# USB_Analog_Controller_24V.net
KiCad netlist of a schematic drawn in EAGLE
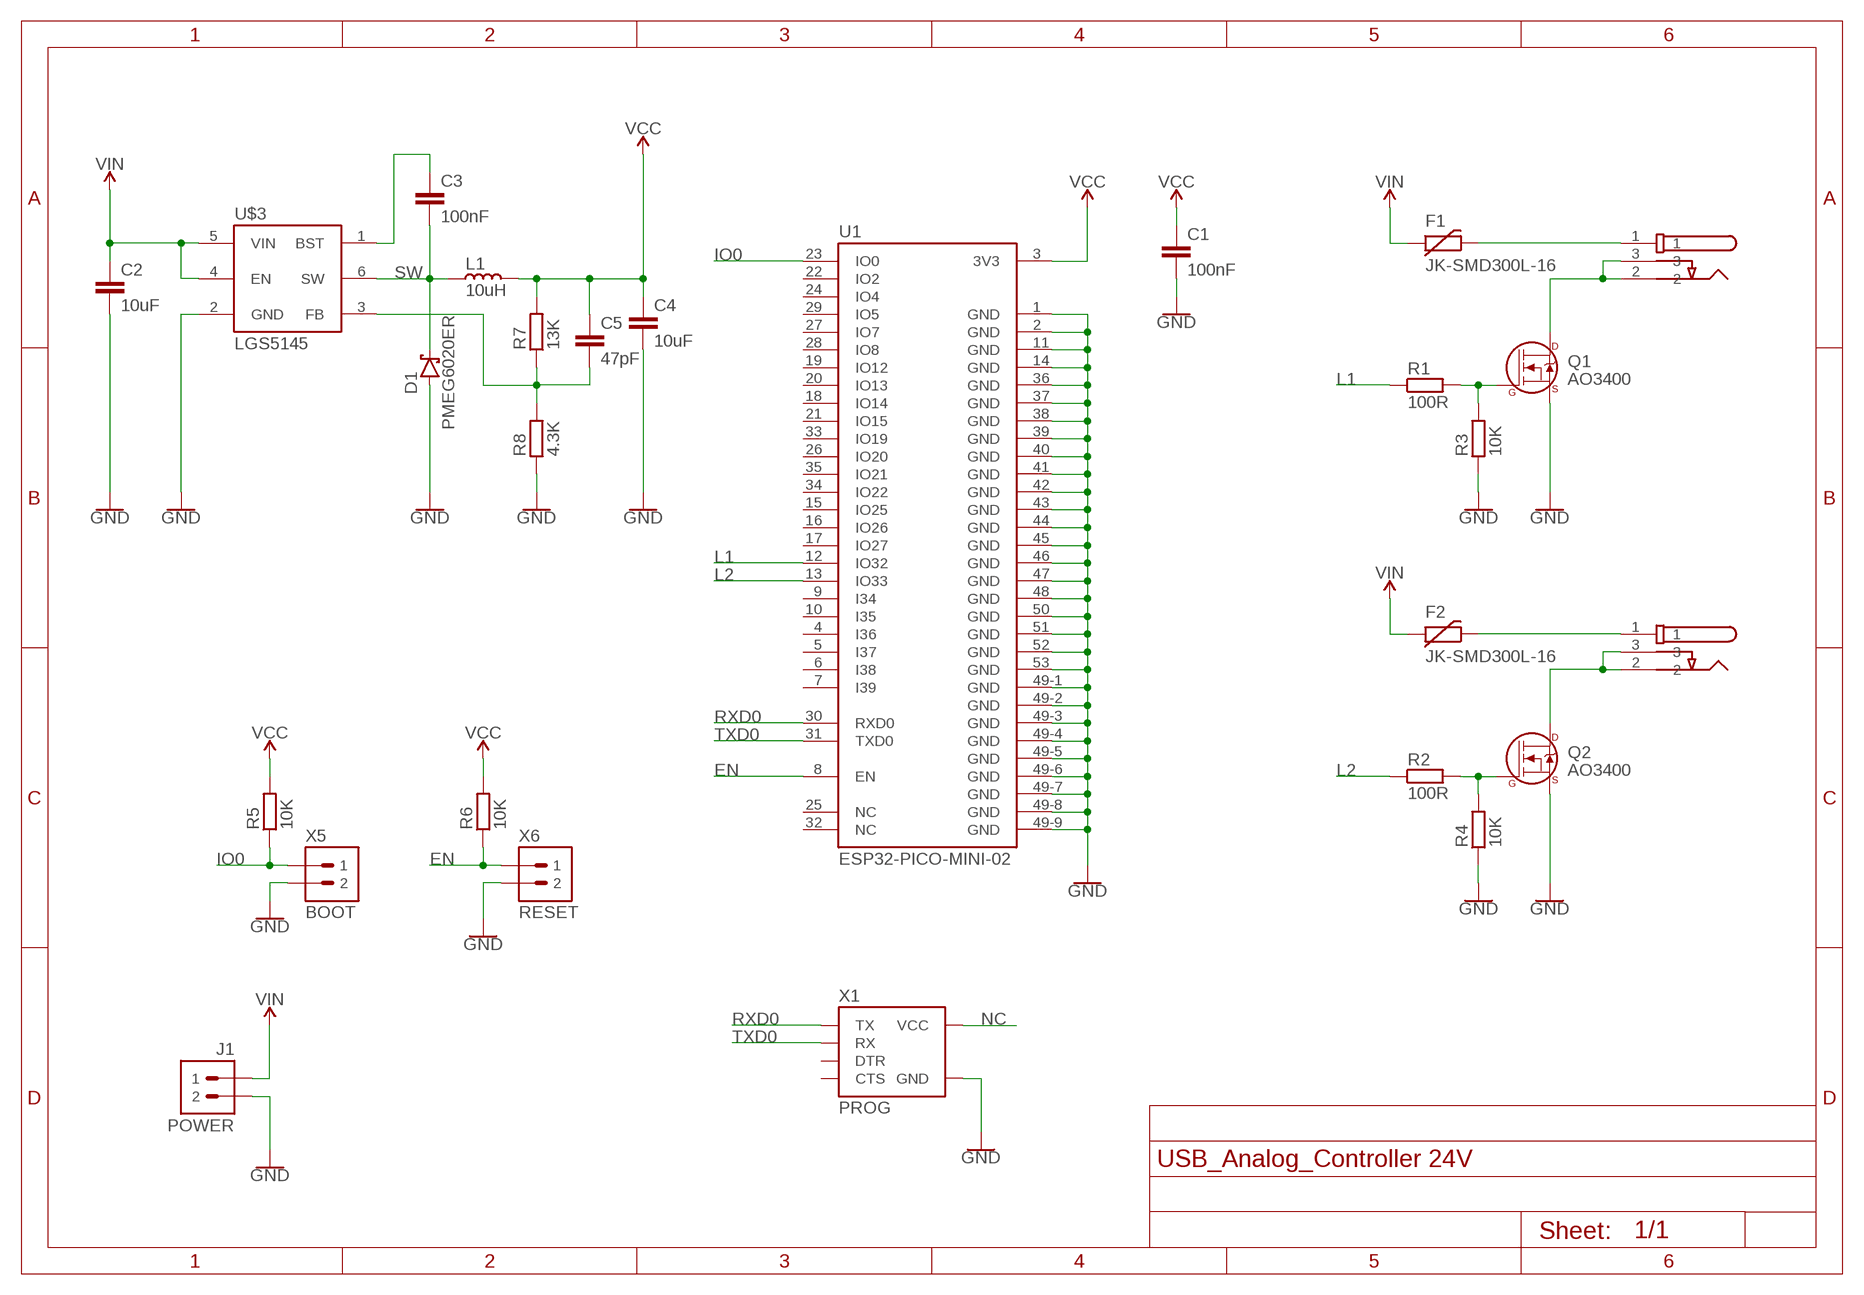
[diagram p0: schematic, sheet 1]

(export (version "E")
  (design (tool "Eeschema 10.0.6"))
  (components
    (comp (ref "C1")
      (value "100nF")
      (footprint "eagle-import:C0603")
      (libsource (lib "eagle-import") (part "CAPC0603"))
    )
    (comp (ref "C2")
      (value "10uF")
      (footprint "eagle-import:C0603")
      (libsource (lib "eagle-import") (part "CAPC0603"))
    )
    (comp (ref "C3")
      (value "100nF")
      (footprint "eagle-import:C0603")
      (libsource (lib "eagle-import") (part "CAPC0603"))
    )
    (comp (ref "C4")
      (value "10uF")
      (footprint "eagle-import:C0603")
      (libsource (lib "eagle-import") (part "CAPC0603"))
    )
    (comp (ref "C5")
      (value "47pF")
      (footprint "eagle-import:C0603")
      (libsource (lib "eagle-import") (part "CAPC0603"))
    )
    (comp (ref "D1")
      (value "PMEG6020ER")
      (footprint "eagle-import:SOD-123FL")
      (libsource (lib "eagle-import") (part "DIODE-SCHOTTKYSOD123FL"))
    )
    (comp (ref "F1")
      (value "JK-SMD300L-16")
      (footprint "eagle-import:JK-SMD300")
      (libsource (lib "eagle-import") (part "PTCJK-SMD300"))
    )
    (comp (ref "F2")
      (value "JK-SMD300L-16")
      (footprint "eagle-import:JK-SMD300")
      (libsource (lib "eagle-import") (part "PTCJK-SMD300"))
    )
    (comp (ref "J1")
      (value "POWER")
      (footprint "eagle-import:TERMINAL-5.08-2P")
      (libsource (lib "eagle-import") (part "TERMINAL-1X02-5.08"))
    )
    (comp (ref "L1")
      (value "10uH")
      (footprint "eagle-import:YJYCOIN-YNR4062")
      (libsource (lib "eagle-import") (part "IND-YJYCOIN-YNR4062"))
    )
    (comp (ref "Q1")
      (value "AO3400")
      (footprint "eagle-import:SOT23-3")
      (libsource (lib "eagle-import") (part "MOSFET-NCHSOT23-3"))
    )
    (comp (ref "Q2")
      (value "AO3400")
      (footprint "eagle-import:SOT23-3")
      (libsource (lib "eagle-import") (part "MOSFET-NCHSOT23-3"))
    )
    (comp (ref "R1")
      (value "100R")
      (footprint "eagle-import:R0603")
      (libsource (lib "eagle-import") (part "RESISTOR0603"))
    )
    (comp (ref "R2")
      (value "100R")
      (footprint "eagle-import:R0603")
      (libsource (lib "eagle-import") (part "RESISTOR0603"))
    )
    (comp (ref "R3")
      (value "10K")
      (footprint "eagle-import:R0603")
      (libsource (lib "eagle-import") (part "RESISTOR0603"))
    )
    (comp (ref "R4")
      (value "10K")
      (footprint "eagle-import:R0603")
      (libsource (lib "eagle-import") (part "RESISTOR0603"))
    )
    (comp (ref "R5")
      (value "10K")
      (footprint "eagle-import:R0603")
      (libsource (lib "eagle-import") (part "RESISTOR0603"))
    )
    (comp (ref "R6")
      (value "10K")
      (footprint "eagle-import:R0603")
      (libsource (lib "eagle-import") (part "RESISTOR0603"))
    )
    (comp (ref "R7")
      (value "13K")
      (footprint "eagle-import:R0603")
      (libsource (lib "eagle-import") (part "RESISTOR0603"))
    )
    (comp (ref "R8")
      (value "4.3K")
      (footprint "eagle-import:R0603")
      (libsource (lib "eagle-import") (part "RESISTOR0603"))
    )
    (comp (ref "U$3")
      (value "LGS5145")
      (footprint "eagle-import:SOT23-6")
      (libsource (lib "eagle-import") (part "LEGEND-SI-LGS5145"))
    )
    (comp (ref "U1")
      (value "ESP32-PICO-MINI-02")
      (footprint "eagle-import:ESP32-PICO-MINI-02")
      (libsource (lib "eagle-import") (part "ESP32-PICO-MINI-02"))
    )
    (comp (ref "X1")
      (value "PROG")
      (footprint "eagle-import:FTDI232-1X06")
      (libsource (lib "eagle-import") (part "HEADER-FTDI232"))
    )
    (comp (ref "X2")
      (value "L1")
      (footprint "eagle-import:XKB-DC-005-5A-2.0")
      (libsource (lib "eagle-import") (part "XKB-DC-005-5A-2.0"))
    )
    (comp (ref "X3")
      (value "L2")
      (footprint "eagle-import:XKB-DC-005-5A-2.0")
      (libsource (lib "eagle-import") (part "XKB-DC-005-5A-2.0"))
    )
    (comp (ref "X5")
      (value "BOOT")
      (footprint "eagle-import:1X02-2.54")
      (libsource (lib "eagle-import") (part "HEADER-1X02-2.54"))
    )
    (comp (ref "X6")
      (value "RESET")
      (footprint "eagle-import:1X02-2.54")
      (libsource (lib "eagle-import") (part "HEADER-1X02-2.54"))
    )
  )
  (nets
    (net (code "1") (name "/EN") (class "Default")
      (node (ref "R6") (pin "1") (pinfunction "1_1") (pintype "passive"))
      (node (ref "U1") (pin "8") (pinfunction "EN_8") (pintype "bidirectional"))
      (node (ref "X6") (pin "1") (pinfunction "1_1") (pintype "passive"))
    )
    (net (code "2") (name "/IO0") (class "Default")
      (node (ref "R5") (pin "1") (pinfunction "1_1") (pintype "passive"))
      (node (ref "U1") (pin "23") (pinfunction "IO0_23") (pintype "bidirectional"))
      (node (ref "X5") (pin "1") (pinfunction "1_1") (pintype "passive"))
    )
    (net (code "3") (name "/L1") (class "Default")
      (node (ref "R1") (pin "1") (pinfunction "1_1") (pintype "passive"))
      (node (ref "U1") (pin "12") (pinfunction "IO32_12") (pintype "bidirectional"))
    )
    (net (code "4") (name "/L2") (class "Default")
      (node (ref "R2") (pin "1") (pinfunction "1_1") (pintype "passive"))
      (node (ref "U1") (pin "13") (pinfunction "IO33_13") (pintype "bidirectional"))
    )
    (net (code "5") (name "/NC") (class "Default")
      (node (ref "X1") (pin "VCC") (pinfunction "VCC_VCC") (pintype "power_in"))
    )
    (net (code "6") (name "/RXD0") (class "Default")
      (node (ref "U1") (pin "30") (pinfunction "RXD0_30") (pintype "bidirectional"))
      (node (ref "X1") (pin "TX") (pinfunction "TX_TX") (pintype "output"))
    )
    (net (code "7") (name "/SW") (class "Default")
      (node (ref "C3") (pin "2") (pinfunction "2_2") (pintype "passive"))
      (node (ref "D1") (pin "C") (pinfunction "C_C") (pintype "passive"))
      (node (ref "L1") (pin "1") (pinfunction "1_1") (pintype "passive"))
      (node (ref "U$3") (pin "6") (pinfunction "SW_6") (pintype "bidirectional"))
    )
    (net (code "8") (name "/TXD0") (class "Default")
      (node (ref "U1") (pin "31") (pinfunction "TXD0_31") (pintype "bidirectional"))
      (node (ref "X1") (pin "RX") (pinfunction "RX_RX") (pintype "input"))
    )
    (net (code "9") (name "GND") (class "Default")
      (node (ref "C1") (pin "2") (pinfunction "2_2") (pintype "passive"))
      (node (ref "C2") (pin "2") (pinfunction "2_2") (pintype "passive"))
      (node (ref "C4") (pin "2") (pinfunction "2_2") (pintype "passive"))
      (node (ref "D1") (pin "A") (pinfunction "A_A") (pintype "passive"))
      (node (ref "J1") (pin "P$2") (pinfunction "2_P$2") (pintype "passive"))
      (node (ref "Q1") (pin "2") (pinfunction "S_2") (pintype "bidirectional"))
      (node (ref "Q2") (pin "2") (pinfunction "S_2") (pintype "bidirectional"))
      (node (ref "R3") (pin "1") (pinfunction "1_1") (pintype "passive"))
      (node (ref "R4") (pin "1") (pinfunction "1_1") (pintype "passive"))
      (node (ref "R8") (pin "1") (pinfunction "1_1") (pintype "passive"))
      (node (ref "U$3") (pin "2") (pinfunction "GND_2") (pintype "bidirectional"))
      (node (ref "U1") (pin "1") (pinfunction "GND_1") (pintype "bidirectional"))
      (node (ref "U1") (pin "11") (pinfunction "GND_11") (pintype "bidirectional"))
      (node (ref "U1") (pin "14") (pinfunction "GND_14") (pintype "bidirectional"))
      (node (ref "U1") (pin "2") (pinfunction "GND_2") (pintype "bidirectional"))
      (node (ref "U1") (pin "36") (pinfunction "GND_36") (pintype "bidirectional"))
      (node (ref "U1") (pin "37") (pinfunction "GND_37") (pintype "bidirectional"))
      (node (ref "U1") (pin "38") (pinfunction "GND_38") (pintype "bidirectional"))
      (node (ref "U1") (pin "39") (pinfunction "GND_39") (pintype "bidirectional"))
      (node (ref "U1") (pin "40") (pinfunction "GND_40") (pintype "bidirectional"))
      (node (ref "U1") (pin "41") (pinfunction "GND_41") (pintype "bidirectional"))
      (node (ref "U1") (pin "42") (pinfunction "GND_42") (pintype "bidirectional"))
      (node (ref "U1") (pin "43") (pinfunction "GND_43") (pintype "bidirectional"))
      (node (ref "U1") (pin "44") (pinfunction "GND_44") (pintype "bidirectional"))
      (node (ref "U1") (pin "45") (pinfunction "GND_45") (pintype "bidirectional"))
      (node (ref "U1") (pin "46") (pinfunction "GND_46") (pintype "bidirectional"))
      (node (ref "U1") (pin "47") (pinfunction "GND_47") (pintype "bidirectional"))
      (node (ref "U1") (pin "48") (pinfunction "GND_48") (pintype "bidirectional"))
      (node (ref "U1") (pin "49-1") (pinfunction "GND_49-1") (pintype "bidirectional"))
      (node (ref "U1") (pin "49-2") (pinfunction "GND_49-2") (pintype "bidirectional"))
      (node (ref "U1") (pin "49-3") (pinfunction "GND_49-3") (pintype "bidirectional"))
      (node (ref "U1") (pin "49-4") (pinfunction "GND_49-4") (pintype "bidirectional"))
      (node (ref "U1") (pin "49-5") (pinfunction "GND_49-5") (pintype "bidirectional"))
      (node (ref "U1") (pin "49-6") (pinfunction "GND_49-6") (pintype "bidirectional"))
      (node (ref "U1") (pin "49-7") (pinfunction "GND_49-7") (pintype "bidirectional"))
      (node (ref "U1") (pin "49-8") (pinfunction "GND_49-8") (pintype "bidirectional"))
      (node (ref "U1") (pin "49-9") (pinfunction "GND_49-9") (pintype "bidirectional"))
      (node (ref "U1") (pin "50") (pinfunction "GND_50") (pintype "bidirectional"))
      (node (ref "U1") (pin "51") (pinfunction "GND_51") (pintype "bidirectional"))
      (node (ref "U1") (pin "52") (pinfunction "GND_52") (pintype "bidirectional"))
      (node (ref "U1") (pin "53") (pinfunction "GND_53") (pintype "bidirectional"))
      (node (ref "X1") (pin "GND") (pinfunction "GND_GND") (pintype "power_in"))
      (node (ref "X5") (pin "2") (pinfunction "2_2") (pintype "passive"))
      (node (ref "X6") (pin "2") (pinfunction "2_2") (pintype "passive"))
    )
    (net (code "10") (name "Net-(F1-2)") (class "Default")
      (node (ref "F1") (pin "B") (pinfunction "2_B") (pintype "bidirectional"))
      (node (ref "X2") (pin "1") (pinfunction "1_1") (pintype "bidirectional"))
    )
    (net (code "11") (name "Net-(F2-2)") (class "Default")
      (node (ref "F2") (pin "B") (pinfunction "2_B") (pintype "bidirectional"))
      (node (ref "X3") (pin "1") (pinfunction "1_1") (pintype "bidirectional"))
    )
    (net (code "12") (name "Net-(Q1-D)") (class "Default")
      (node (ref "Q1") (pin "3") (pinfunction "D_3") (pintype "bidirectional"))
      (node (ref "X2") (pin "2") (pinfunction "2_2") (pintype "bidirectional"))
      (node (ref "X2") (pin "3") (pinfunction "3_3") (pintype "bidirectional"))
    )
    (net (code "13") (name "Net-(Q1-G)") (class "Default")
      (node (ref "Q1") (pin "1") (pinfunction "G_1") (pintype "bidirectional"))
      (node (ref "R1") (pin "2") (pinfunction "2_2") (pintype "passive"))
      (node (ref "R3") (pin "2") (pinfunction "2_2") (pintype "passive"))
    )
    (net (code "14") (name "Net-(Q2-D)") (class "Default")
      (node (ref "Q2") (pin "3") (pinfunction "D_3") (pintype "bidirectional"))
      (node (ref "X3") (pin "2") (pinfunction "2_2") (pintype "bidirectional"))
      (node (ref "X3") (pin "3") (pinfunction "3_3") (pintype "bidirectional"))
    )
    (net (code "15") (name "Net-(Q2-G)") (class "Default")
      (node (ref "Q2") (pin "1") (pinfunction "G_1") (pintype "bidirectional"))
      (node (ref "R2") (pin "2") (pinfunction "2_2") (pintype "passive"))
      (node (ref "R4") (pin "2") (pinfunction "2_2") (pintype "passive"))
    )
    (net (code "16") (name "Net-(U$3-BST)") (class "Default")
      (node (ref "C3") (pin "1") (pinfunction "1_1") (pintype "passive"))
      (node (ref "U$3") (pin "1") (pinfunction "BST_1") (pintype "bidirectional"))
    )
    (net (code "17") (name "Net-(U$3-FB)") (class "Default")
      (node (ref "C5") (pin "2") (pinfunction "2_2") (pintype "passive"))
      (node (ref "R7") (pin "1") (pinfunction "1_1") (pintype "passive"))
      (node (ref "R8") (pin "2") (pinfunction "2_2") (pintype "passive"))
      (node (ref "U$3") (pin "3") (pinfunction "FB_3") (pintype "bidirectional"))
    )
    (net (code "18") (name "VCC") (class "Default")
      (node (ref "C1") (pin "1") (pinfunction "1_1") (pintype "passive"))
      (node (ref "C4") (pin "1") (pinfunction "1_1") (pintype "passive"))
      (node (ref "C5") (pin "1") (pinfunction "1_1") (pintype "passive"))
      (node (ref "L1") (pin "2") (pinfunction "2_2") (pintype "passive"))
      (node (ref "R5") (pin "2") (pinfunction "2_2") (pintype "passive"))
      (node (ref "R6") (pin "2") (pinfunction "2_2") (pintype "passive"))
      (node (ref "R7") (pin "2") (pinfunction "2_2") (pintype "passive"))
      (node (ref "U1") (pin "3") (pinfunction "3V3_3") (pintype "bidirectional"))
    )
    (net (code "19") (name "VIN") (class "Default")
      (node (ref "C2") (pin "1") (pinfunction "1_1") (pintype "passive"))
      (node (ref "F1") (pin "A") (pinfunction "1_A") (pintype "bidirectional"))
      (node (ref "F2") (pin "A") (pinfunction "1_A") (pintype "bidirectional"))
      (node (ref "J1") (pin "P$1") (pinfunction "1_P$1") (pintype "passive"))
      (node (ref "U$3") (pin "4") (pinfunction "EN_4") (pintype "bidirectional"))
      (node (ref "U$3") (pin "5") (pinfunction "VIN_5") (pintype "bidirectional"))
    )
    (net (code "20") (name "unconnected-(U1-I34-Pad9)") (class "Default")
      (node (ref "U1") (pin "9") (pinfunction "I34_9") (pintype "bidirectional"))
    )
    (net (code "21") (name "unconnected-(U1-I35-Pad10)") (class "Default")
      (node (ref "U1") (pin "10") (pinfunction "I35_10") (pintype "bidirectional"))
    )
    (net (code "22") (name "unconnected-(U1-I36-Pad4)") (class "Default")
      (node (ref "U1") (pin "4") (pinfunction "I36_4") (pintype "bidirectional"))
    )
    (net (code "23") (name "unconnected-(U1-I37-Pad5)") (class "Default")
      (node (ref "U1") (pin "5") (pinfunction "I37_5") (pintype "bidirectional"))
    )
    (net (code "24") (name "unconnected-(U1-I38-Pad6)") (class "Default")
      (node (ref "U1") (pin "6") (pinfunction "I38_6") (pintype "bidirectional"))
    )
    (net (code "25") (name "unconnected-(U1-I39-Pad7)") (class "Default")
      (node (ref "U1") (pin "7") (pinfunction "I39_7") (pintype "bidirectional"))
    )
    (net (code "26") (name "unconnected-(U1-IO2-Pad22)") (class "Default")
      (node (ref "U1") (pin "22") (pinfunction "IO2_22") (pintype "bidirectional"))
    )
    (net (code "27") (name "unconnected-(U1-IO4-Pad24)") (class "Default")
      (node (ref "U1") (pin "24") (pinfunction "IO4_24") (pintype "bidirectional"))
    )
    (net (code "28") (name "unconnected-(U1-IO5-Pad29)") (class "Default")
      (node (ref "U1") (pin "29") (pinfunction "IO5_29") (pintype "bidirectional"))
    )
    (net (code "29") (name "unconnected-(U1-IO7-Pad27)") (class "Default")
      (node (ref "U1") (pin "27") (pinfunction "IO7_27") (pintype "bidirectional"))
    )
    (net (code "30") (name "unconnected-(U1-IO8-Pad28)") (class "Default")
      (node (ref "U1") (pin "28") (pinfunction "IO8_28") (pintype "bidirectional"))
    )
    (net (code "31") (name "unconnected-(U1-IO12-Pad19)") (class "Default")
      (node (ref "U1") (pin "19") (pinfunction "IO12_19") (pintype "bidirectional"))
    )
    (net (code "32") (name "unconnected-(U1-IO13-Pad20)") (class "Default")
      (node (ref "U1") (pin "20") (pinfunction "IO13_20") (pintype "bidirectional"))
    )
    (net (code "33") (name "unconnected-(U1-IO14-Pad18)") (class "Default")
      (node (ref "U1") (pin "18") (pinfunction "IO14_18") (pintype "bidirectional"))
    )
    (net (code "34") (name "unconnected-(U1-IO15-Pad21)") (class "Default")
      (node (ref "U1") (pin "21") (pinfunction "IO15_21") (pintype "bidirectional"))
    )
    (net (code "35") (name "unconnected-(U1-IO19-Pad33)") (class "Default")
      (node (ref "U1") (pin "33") (pinfunction "IO19_33") (pintype "bidirectional"))
    )
    (net (code "36") (name "unconnected-(U1-IO20-Pad26)") (class "Default")
      (node (ref "U1") (pin "26") (pinfunction "IO20_26") (pintype "bidirectional"))
    )
    (net (code "37") (name "unconnected-(U1-IO21-Pad35)") (class "Default")
      (node (ref "U1") (pin "35") (pinfunction "IO21_35") (pintype "bidirectional"))
    )
    (net (code "38") (name "unconnected-(U1-IO22-Pad34)") (class "Default")
      (node (ref "U1") (pin "34") (pinfunction "IO22_34") (pintype "bidirectional"))
    )
    (net (code "39") (name "unconnected-(U1-IO25-Pad15)") (class "Default")
      (node (ref "U1") (pin "15") (pinfunction "IO25_15") (pintype "bidirectional"))
    )
    (net (code "40") (name "unconnected-(U1-IO26-Pad16)") (class "Default")
      (node (ref "U1") (pin "16") (pinfunction "IO26_16") (pintype "bidirectional"))
    )
    (net (code "41") (name "unconnected-(U1-IO27-Pad17)") (class "Default")
      (node (ref "U1") (pin "17") (pinfunction "IO27_17") (pintype "bidirectional"))
    )
    (net (code "42") (name "unconnected-(U1-NC-Pad25)") (class "Default")
      (node (ref "U1") (pin "25") (pinfunction "NC_25") (pintype "bidirectional"))
    )
    (net (code "43") (name "unconnected-(U1-NC-Pad32)") (class "Default")
      (node (ref "U1") (pin "32") (pinfunction "NC_32") (pintype "bidirectional"))
    )
    (net (code "44") (name "unconnected-(X1-PadCTS)") (class "Default")
      (node (ref "X1") (pin "CTS") (pinfunction "CTS_CTS") (pintype "output"))
    )
    (net (code "45") (name "unconnected-(X1-PadDTR)") (class "Default")
      (node (ref "X1") (pin "DTR") (pinfunction "DTR_DTR") (pintype "output"))
    )
  )
)
